# sensor_design.net
KiCad netlist of a schematic drawn in EasyEDA Pro
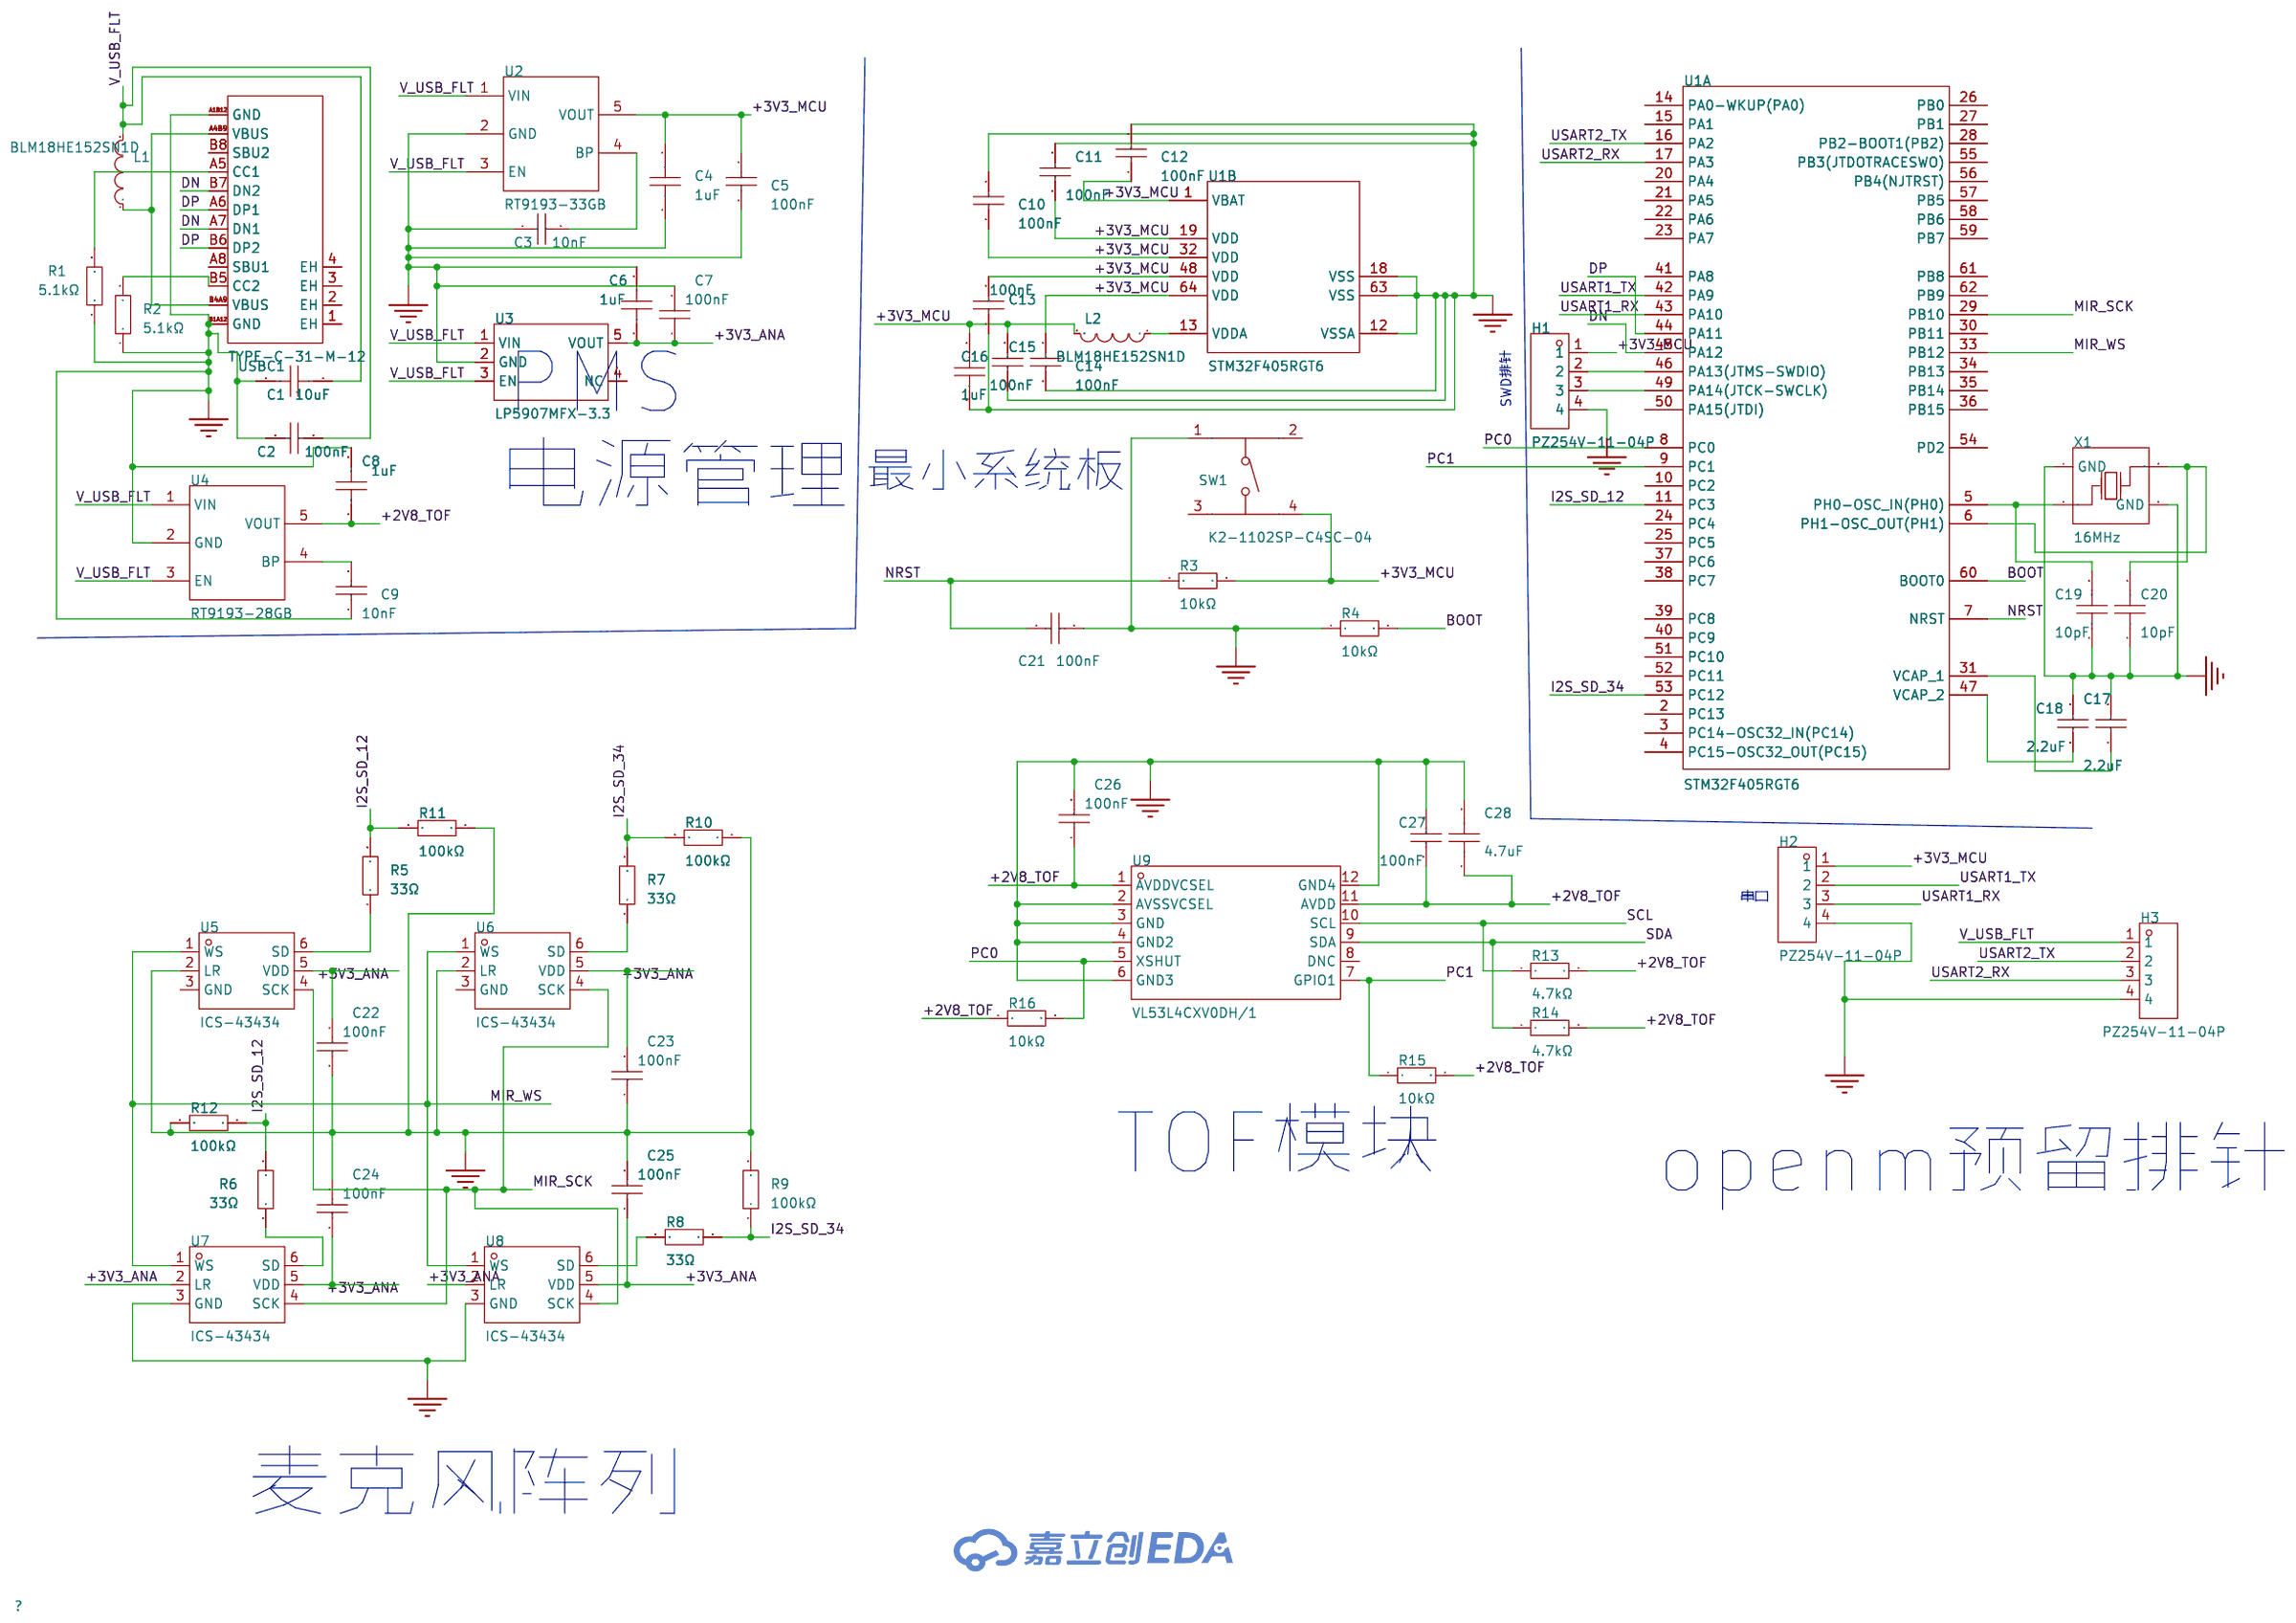
[diagram p0: schematic sheet]

(export (version "E")
  (design (tool "Eeschema 10.0.6"))
  (components
    (comp (ref "C1")
      (value "10uF")
      (footprint "easyedapro:C0805")
      (description "容值:10uF;精度:±10%;额定电压:16V;材质(温度系数):X5R;")
      (fields
        (field (name "Manufacturer Part") "GRM21BR61C106KE15L")
        (field (name "Manufacturer") "muRata(村田)")
      )
      (libsource (lib "easyedapro") (part "GRM21BR61C106KE15L"))
    )
    (comp (ref "C2")
      (value "100nF")
      (footprint "easyedapro:C0603")
      (description "容值:100nF;精度:±10%;额定电压:25V;温度系数:X7R;")
      (fields
        (field (name "Manufacturer Part") "CL10B104KA8NNNC")
        (field (name "Manufacturer") "SAMSUNG(三星)")
      )
      (libsource (lib "easyedapro") (part "CL10B104KA8NNNC"))
    )
    (comp (ref "C3")
      (value "10nF")
      (footprint "easyedapro:C0603")
      (description "容值:100nF;精度:±10%;额定电压:25V;温度系数:X7R;")
      (fields
        (field (name "Manufacturer Part") "CL10B104KA8NNNC")
        (field (name "Manufacturer") "SAMSUNG(三星)")
      )
      (libsource (lib "easyedapro") (part "CL10B104KA8NNNC"))
    )
    (comp (ref "C4")
      (value "1uF")
      (footprint "easyedapro:C0603")
      (description "容值:1uF;精度:±10%;额定电压:16V;温度系数:X7R;")
      (fields
        (field (name "Manufacturer Part") "GRM188R71C105KE15D")
        (field (name "Manufacturer") "muRata(村田)")
      )
      (libsource (lib "easyedapro") (part "GRM188R71C105KE15D"))
    )
    (comp (ref "C5")
      (value "100nF")
      (footprint "easyedapro:C0603")
      (description "容值:100nF;精度:±10%;额定电压:25V;温度系数:X7R;")
      (fields
        (field (name "Manufacturer Part") "CL10B104KA8NNNC")
        (field (name "Manufacturer") "SAMSUNG(三星)")
      )
      (libsource (lib "easyedapro") (part "CL10B104KA8NNNC"))
    )
    (comp (ref "C6")
      (value "1uF")
      (footprint "easyedapro:C0603")
      (description "容值:1uF;精度:±10%;额定电压:16V;温度系数:X7R;")
      (fields
        (field (name "Manufacturer Part") "GRM188R71C105KE15D")
        (field (name "Manufacturer") "muRata(村田)")
      )
      (libsource (lib "easyedapro") (part "GRM188R71C105KE15D"))
    )
    (comp (ref "C7")
      (value "100nF")
      (footprint "easyedapro:C0603")
      (description "容值:100nF;精度:±10%;额定电压:25V;温度系数:X7R;")
      (fields
        (field (name "Manufacturer Part") "CL10B104KA8NNNC")
        (field (name "Manufacturer") "SAMSUNG(三星)")
      )
      (libsource (lib "easyedapro") (part "CL10B104KA8NNNC"))
    )
    (comp (ref "C8")
      (value "1uF")
      (footprint "easyedapro:C0603")
      (description "容值:1uF;精度:±10%;额定电压:16V;温度系数:X7R;")
      (fields
        (field (name "Manufacturer Part") "GRM188R71C105KE15D")
        (field (name "Manufacturer") "muRata(村田)")
      )
      (libsource (lib "easyedapro") (part "GRM188R71C105KE15D"))
    )
    (comp (ref "C9")
      (value "10nF")
      (footprint "easyedapro:C0603")
      (description "容值:100nF;精度:±10%;额定电压:25V;温度系数:X7R;")
      (fields
        (field (name "Manufacturer Part") "CL10B104KA8NNNC")
        (field (name "Manufacturer") "SAMSUNG(三星)")
      )
      (libsource (lib "easyedapro") (part "CL10B104KA8NNNC"))
    )
    (comp (ref "C10")
      (value "100nF")
      (footprint "easyedapro:C0603")
      (description "容值:100nF;精度:±10%;额定电压:25V;温度系数:X7R;")
      (fields
        (field (name "Manufacturer Part") "CL10B104KA8NNNC")
        (field (name "Manufacturer") "SAMSUNG(三星)")
      )
      (libsource (lib "easyedapro") (part "CL10B104KA8NNNC"))
    )
    (comp (ref "C11")
      (value "100nF")
      (footprint "easyedapro:C0603")
      (description "容值:100nF;精度:±10%;额定电压:25V;温度系数:X7R;")
      (fields
        (field (name "Manufacturer Part") "CL10B104KA8NNNC")
        (field (name "Manufacturer") "SAMSUNG(三星)")
      )
      (libsource (lib "easyedapro") (part "CL10B104KA8NNNC"))
    )
    (comp (ref "C12")
      (value "100nF")
      (footprint "easyedapro:C0603")
      (description "容值:100nF;精度:±10%;额定电压:25V;温度系数:X7R;")
      (fields
        (field (name "Manufacturer Part") "CL10B104KA8NNNC")
        (field (name "Manufacturer") "SAMSUNG(三星)")
      )
      (libsource (lib "easyedapro") (part "CL10B104KA8NNNC"))
    )
    (comp (ref "C13")
      (value "100nF")
      (footprint "easyedapro:C0603")
      (description "容值:100nF;精度:±10%;额定电压:25V;温度系数:X7R;")
      (fields
        (field (name "Manufacturer Part") "CL10B104KA8NNNC")
        (field (name "Manufacturer") "SAMSUNG(三星)")
      )
      (libsource (lib "easyedapro") (part "CL10B104KA8NNNC"))
    )
    (comp (ref "C14")
      (value "100nF")
      (footprint "easyedapro:C0603")
      (description "容值:100nF;精度:±10%;额定电压:25V;温度系数:X7R;")
      (fields
        (field (name "Manufacturer Part") "CL10B104KA8NNNC")
        (field (name "Manufacturer") "SAMSUNG(三星)")
      )
      (libsource (lib "easyedapro") (part "CL10B104KA8NNNC"))
    )
    (comp (ref "C15")
      (value "100nF")
      (footprint "easyedapro:C0603")
      (description "容值:100nF;精度:±10%;额定电压:25V;温度系数:X7R;")
      (fields
        (field (name "Manufacturer Part") "CL10B104KA8NNNC")
        (field (name "Manufacturer") "SAMSUNG(三星)")
      )
      (libsource (lib "easyedapro") (part "CL10B104KA8NNNC"))
    )
    (comp (ref "C16")
      (value "1uF")
      (footprint "easyedapro:C0603")
      (description "容值:1uF;精度:±10%;额定电压:16V;温度系数:X7R;")
      (fields
        (field (name "Manufacturer Part") "GRM188R71C105KE15D")
        (field (name "Manufacturer") "muRata(村田)")
      )
      (libsource (lib "easyedapro") (part "GRM188R71C105KE15D"))
    )
    (comp (ref "C17")
      (value "2.2uF")
      (footprint "easyedapro:C0603")
      (description "容值:2.2uF;精度:±10%;额定电压:10V;温度系数:X5R;")
      (fields
        (field (name "Manufacturer Part") "CL10A225KP8NNNC")
        (field (name "Manufacturer") "SAMSUNG(三星)")
      )
      (libsource (lib "easyedapro") (part "CL10A225KP8NNNC"))
    )
    (comp (ref "C18")
      (value "2.2uF")
      (footprint "easyedapro:C0603")
      (description "容值:2.2uF;精度:±10%;额定电压:10V;温度系数:X5R;")
      (fields
        (field (name "Manufacturer Part") "CL10A225KP8NNNC")
        (field (name "Manufacturer") "SAMSUNG(三星)")
      )
      (libsource (lib "easyedapro") (part "CL10A225KP8NNNC"))
    )
    (comp (ref "C19")
      (value "10pF")
      (footprint "easyedapro:C0402")
      (description "容值:10pF;精度:±1%;额定电压:50V;温度系数:C0G;")
      (fields
        (field (name "Manufacturer Part") "GJM1555C1H100FB01D")
        (field (name "Manufacturer") "muRata(村田)")
      )
      (libsource (lib "easyedapro") (part "GJM1555C1H100FB01D"))
    )
    (comp (ref "C20")
      (value "10pF")
      (footprint "easyedapro:C0402")
      (description "容值:10pF;精度:±1%;额定电压:50V;温度系数:C0G;")
      (fields
        (field (name "Manufacturer Part") "GJM1555C1H100FB01D")
        (field (name "Manufacturer") "muRata(村田)")
      )
      (libsource (lib "easyedapro") (part "GJM1555C1H100FB01D"))
    )
    (comp (ref "C21")
      (value "100nF")
      (footprint "easyedapro:C0603")
      (description "容值:100nF;精度:±10%;额定电压:25V;温度系数:X7R;")
      (fields
        (field (name "Manufacturer Part") "CL10B104KA8NNNC")
        (field (name "Manufacturer") "SAMSUNG(三星)")
      )
      (libsource (lib "easyedapro") (part "CL10B104KA8NNNC"))
    )
    (comp (ref "C22")
      (value "100nF")
      (footprint "easyedapro:C0603")
      (description "容值:100nF;精度:±10%;额定电压:25V;温度系数:X7R;")
      (fields
        (field (name "Manufacturer Part") "CL10B104KA8NNNC")
        (field (name "Manufacturer") "SAMSUNG(三星)")
      )
      (libsource (lib "easyedapro") (part "CL10B104KA8NNNC"))
    )
    (comp (ref "C23")
      (value "100nF")
      (footprint "easyedapro:C0603")
      (description "容值:100nF;精度:±10%;额定电压:25V;温度系数:X7R;")
      (fields
        (field (name "Manufacturer Part") "CL10B104KA8NNNC")
        (field (name "Manufacturer") "SAMSUNG(三星)")
      )
      (libsource (lib "easyedapro") (part "CL10B104KA8NNNC"))
    )
    (comp (ref "C24")
      (value "100nF")
      (footprint "easyedapro:C0603")
      (description "容值:100nF;精度:±10%;额定电压:25V;温度系数:X7R;")
      (fields
        (field (name "Manufacturer Part") "CL10B104KA8NNNC")
        (field (name "Manufacturer") "SAMSUNG(三星)")
      )
      (libsource (lib "easyedapro") (part "CL10B104KA8NNNC"))
    )
    (comp (ref "C25")
      (value "100nF")
      (footprint "easyedapro:C0603")
      (description "容值:100nF;精度:±10%;额定电压:25V;温度系数:X7R;")
      (fields
        (field (name "Manufacturer Part") "CL10B104KA8NNNC")
        (field (name "Manufacturer") "SAMSUNG(三星)")
      )
      (libsource (lib "easyedapro") (part "CL10B104KA8NNNC"))
    )
    (comp (ref "C26")
      (value "100nF")
      (footprint "easyedapro:C0603")
      (description "容值:100nF;精度:±10%;额定电压:25V;温度系数:X7R;")
      (fields
        (field (name "Manufacturer Part") "CGA0402X7R104K250GT")
        (field (name "Manufacturer") "HRE(芯声)")
      )
      (libsource (lib "easyedapro") (part "CL10B104KA8NNNC"))
    )
    (comp (ref "C27")
      (value "100nF")
      (footprint "easyedapro:C0603")
      (description "容值:100nF;精度:±10%;额定电压:25V;温度系数:X7R;")
      (fields
        (field (name "Manufacturer Part") "CGA0402X7R104K250GT")
        (field (name "Manufacturer") "HRE(芯声)")
      )
      (libsource (lib "easyedapro") (part "CL10B104KA8NNNC"))
    )
    (comp (ref "C28")
      (value "4.7uF")
      (footprint "easyedapro:C0603")
      (description "容值:4.7uF;精度:±10%;额定电压:16V;温度系数:X7R;")
      (fields
        (field (name "Manufacturer Part") "GRM188Z71C475KE21D")
        (field (name "Manufacturer") "muRata(村田)")
      )
      (libsource (lib "easyedapro") (part "GRM188Z71C475KE21D"))
    )
    (comp (ref "H1")
      (value "PZ254V-11-04P")
      (footprint "easyedapro:HDR-TH_4P-P2.54-V-M")
      (fields (field (name "Manufacturer") "XFCN(兴飞)"))
      (libsource (lib "easyedapro") (part "PZ254V-11-04P_C2691448"))
    )
    (comp (ref "H2")
      (value "PZ254V-11-04P")
      (footprint "easyedapro:HDR-TH_4P-P2.54-V-M")
      (fields (field (name "Manufacturer") "XFCN(兴飞)"))
      (libsource (lib "easyedapro") (part "PZ254V-11-04P_C2691448"))
    )
    (comp (ref "H3")
      (value "PZ254V-11-04P")
      (footprint "easyedapro:HDR-TH_4P-P2.54-V-M")
      (fields (field (name "Manufacturer") "XFCN(兴飞)"))
      (libsource (lib "easyedapro") (part "PZ254V-11-04P_C2691448"))
    )
    (comp (ref "L1")
      (value "BLM18HE152SN1D")
      (footprint "easyedapro:L0603")
      (description "标称阻抗@测试频率:1.5kΩ@100MHz;误差:±25%;直流电阻(RDC):500mΩ;")
      (fields (field (name "Manufacturer") "muRata(村田)"))
      (libsource (lib "easyedapro") (part "BLM18HE152SN1D"))
    )
    (comp (ref "L2")
      (value "BLM18HE152SN1D")
      (footprint "easyedapro:L0603")
      (description "标称阻抗@测试频率:1.5kΩ@100MHz;误差:±25%;直流电阻(RDC):500mΩ;")
      (fields (field (name "Manufacturer") "muRata(村田)"))
      (libsource (lib "easyedapro") (part "BLM18HE152SN1D"))
    )
    (comp (ref "R1")
      (value "5.1kΩ")
      (footprint "easyedapro:R0603")
      (description "电阻类型:厚膜电阻;阻值:5.1kΩ;精度:±1%;功率:100mW;工作电压:75V;温度系数:±100ppm/°C;")
      (fields (field (name "Manufacturer Part") "RC0603FR-075K1L") (field (name "Manufacturer") "YAGEO(国巨)"))
      (libsource (lib "easyedapro") (part "RC0603FR-075K1L"))
    )
    (comp (ref "R2")
      (value "5.1kΩ")
      (footprint "easyedapro:R0603")
      (description "电阻类型:厚膜电阻;阻值:5.1kΩ;精度:±1%;功率:100mW;工作电压:75V;温度系数:±100ppm/°C;")
      (fields (field (name "Manufacturer Part") "RC0603FR-075K1L") (field (name "Manufacturer") "YAGEO(国巨)"))
      (libsource (lib "easyedapro") (part "RC0603FR-075K1L"))
    )
    (comp (ref "R3")
      (value "10kΩ")
      (footprint "easyedapro:R0603")
      (description "电阻类型:厚膜电阻;阻值:10kΩ;精度:±1%;功率:100mW;工作电压:75V;温度系数:±100ppm/°C;")
      (fields
        (field (name "Manufacturer Part") "0603WAF1002T5E")
        (field (name "Manufacturer") "UNI-ROYAL(厚声)")
      )
      (libsource (lib "easyedapro") (part "0603WAF1002T5E"))
    )
    (comp (ref "R4")
      (value "10kΩ")
      (footprint "easyedapro:R0603")
      (description "电阻类型:厚膜电阻;阻值:10kΩ;精度:±1%;功率:100mW;工作电压:75V;温度系数:±100ppm/°C;")
      (fields
        (field (name "Manufacturer Part") "0603WAF1002T5E")
        (field (name "Manufacturer") "UNI-ROYAL(厚声)")
      )
      (libsource (lib "easyedapro") (part "0603WAF1002T5E"))
    )
    (comp (ref "R5")
      (value "33Ω")
      (footprint "easyedapro:R0603")
      (description "电阻类型:厚膜电阻;阻值:3.3kΩ;精度:±1%;功率:100mW;工作电压:75V;温度系数:±100ppm/°C;")
      (fields
        (field (name "Manufacturer Part") "0603WAF330JT5E")
        (field (name "Manufacturer") "UNI-ROYAL(厚声)")
      )
      (libsource (lib "easyedapro") (part "0603WAF3301T5E"))
    )
    (comp (ref "R6")
      (value "33Ω")
      (footprint "easyedapro:R0603")
      (description "电阻类型:厚膜电阻;阻值:3.3kΩ;精度:±1%;功率:100mW;工作电压:75V;温度系数:±100ppm/°C;")
      (fields
        (field (name "Manufacturer Part") "0603WAF330JT5E")
        (field (name "Manufacturer") "UNI-ROYAL(厚声)")
      )
      (libsource (lib "easyedapro") (part "0603WAF3301T5E"))
    )
    (comp (ref "R7")
      (value "33Ω")
      (footprint "easyedapro:R0603")
      (description "电阻类型:厚膜电阻;阻值:3.3kΩ;精度:±1%;功率:100mW;工作电压:75V;温度系数:±100ppm/°C;")
      (fields
        (field (name "Manufacturer Part") "0603WAF330JT5E")
        (field (name "Manufacturer") "UNI-ROYAL(厚声)")
      )
      (libsource (lib "easyedapro") (part "0603WAF3301T5E"))
    )
    (comp (ref "R8")
      (value "33Ω")
      (footprint "easyedapro:R0603")
      (description "电阻类型:厚膜电阻;阻值:3.3kΩ;精度:±1%;功率:100mW;工作电压:75V;温度系数:±100ppm/°C;")
      (fields
        (field (name "Manufacturer Part") "0603WAF330JT5E")
        (field (name "Manufacturer") "UNI-ROYAL(厚声)")
      )
      (libsource (lib "easyedapro") (part "0603WAF3301T5E"))
    )
    (comp (ref "R9")
      (value "100kΩ")
      (footprint "easyedapro:R0603")
      (description "电阻类型:厚膜电阻;阻值:100kΩ;精度:±1%;功率:100mW;工作电压:75V;温度系数:±100ppm/°C;")
      (fields
        (field (name "Manufacturer Part") "0603WAF1003T5E")
        (field (name "Manufacturer") "UNI-ROYAL(厚声)")
      )
      (libsource (lib "easyedapro") (part "0603WAF1003T5E"))
    )
    (comp (ref "R10")
      (value "100kΩ")
      (footprint "easyedapro:R0603")
      (description "电阻类型:厚膜电阻;阻值:100kΩ;精度:±1%;功率:100mW;工作电压:75V;温度系数:±100ppm/°C;")
      (fields
        (field (name "Manufacturer Part") "0603WAF1003T5E")
        (field (name "Manufacturer") "UNI-ROYAL(厚声)")
      )
      (libsource (lib "easyedapro") (part "0603WAF1003T5E"))
    )
    (comp (ref "R11")
      (value "100kΩ")
      (footprint "easyedapro:R0603")
      (description "电阻类型:厚膜电阻;阻值:100kΩ;精度:±1%;功率:100mW;工作电压:75V;温度系数:±100ppm/°C;")
      (fields
        (field (name "Manufacturer Part") "0603WAF1003T5E")
        (field (name "Manufacturer") "UNI-ROYAL(厚声)")
      )
      (libsource (lib "easyedapro") (part "0603WAF1003T5E"))
    )
    (comp (ref "R12")
      (value "100kΩ")
      (footprint "easyedapro:R0603")
      (description "电阻类型:厚膜电阻;阻值:100kΩ;精度:±1%;功率:100mW;工作电压:75V;温度系数:±100ppm/°C;")
      (fields
        (field (name "Manufacturer Part") "0603WAF1003T5E")
        (field (name "Manufacturer") "UNI-ROYAL(厚声)")
      )
      (libsource (lib "easyedapro") (part "0603WAF1003T5E"))
    )
    (comp (ref "R13")
      (value "4.7kΩ")
      (footprint "easyedapro:R0603")
      (description "电阻类型:厚膜电阻;阻值:4.7kΩ;精度:±1%;功率:100mW;工作电压:75V;温度系数:±100ppm/°C;")
      (fields
        (field (name "Manufacturer Part") "0603WAF4701T5E")
        (field (name "Manufacturer") "UNI-ROYAL(厚声)")
      )
      (libsource (lib "easyedapro") (part "0603WAF4701T5E"))
    )
    (comp (ref "R14")
      (value "4.7kΩ")
      (footprint "easyedapro:R0603")
      (description "电阻类型:厚膜电阻;阻值:4.7kΩ;精度:±1%;功率:100mW;工作电压:75V;温度系数:±100ppm/°C;")
      (fields
        (field (name "Manufacturer Part") "0603WAF4701T5E")
        (field (name "Manufacturer") "UNI-ROYAL(厚声)")
      )
      (libsource (lib "easyedapro") (part "0603WAF4701T5E"))
    )
    (comp (ref "R15")
      (value "10kΩ")
      (footprint "easyedapro:R0603")
      (description "电阻类型:厚膜电阻;阻值:10kΩ;精度:±1%;功率:100mW;工作电压:75V;温度系数:±100ppm/°C;")
      (fields
        (field (name "Manufacturer Part") "0603WAF1002T5E")
        (field (name "Manufacturer") "UNI-ROYAL(厚声)")
      )
      (libsource (lib "easyedapro") (part "0603WAF1002T5E"))
    )
    (comp (ref "R16")
      (value "10kΩ")
      (footprint "easyedapro:R0603")
      (description "电阻类型:厚膜电阻;阻值:10kΩ;精度:±1%;功率:100mW;工作电压:75V;温度系数:±100ppm/°C;")
      (fields
        (field (name "Manufacturer Part") "0603WAF1002T5E")
        (field (name "Manufacturer") "UNI-ROYAL(厚声)")
      )
      (libsource (lib "easyedapro") (part "0603WAF1002T5E"))
    )
    (comp (ref "SW1")
      (value "K2-1102SP-C4SC-04")
      (footprint "easyedapro:KEY-SMD_4P-L6.0-W6.0-P4.50-LS9.5-BL")
      (description "电路结构:单刀单掷;按钮形状:圆形按钮;作用力:2.5N;安装方式:立贴;开关长度:6mm;开关宽度:6mm;开关高度:5mm;触点电流:50mA;额定电压:12V;带灯:-;工作寿命:10万次;")
      (fields (field (name "Manufacturer") "韩国韩荣"))
      (libsource (lib "easyedapro") (part "K2-1102SP-C4SC-04"))
    )
    (comp (ref "U1")
      (value "STM32F405RGT6")
      (footprint "easyedapro:LQFP-64_L10.0-W10.0-P0.50-LS12.0-BL")
      (description "CPU内核:ARM-M4;CPU最大主频:168MHz;应用领域:-;")
      (fields (field (name "Manufacturer") "ST(意法半导体)"))
      (libsource (lib "easyedapro") (part "STM32F405RGT6"))
    )
    (comp (ref "U2")
      (value "RT9193-33GB")
      (footprint "easyedapro:SOT-23-5_L3.0-W1.7-P0.95-LS2.8-BL")
      (description "输出类型:固定;工作电压:5.5V;输出电压:3.3V;输出电流:300mA;电源纹波抑制比(PSRR):-50dB@(10kHz);输出极性:正极;")
      (fields (field (name "Manufacturer") "RICHTEK(立锜)"))
      (libsource (lib "easyedapro") (part "RT9193-33GB"))
    )
    (comp (ref "U3")
      (value "LP5907MFX-3.3")
      (footprint "easyedapro:SOT-23-5_L3.0-W1.7-P0.95-LS2.8-BR")
      (description "输出类型:固定;工作电压:5.5V;输出电压:3.3V;输出电流:300mA;电源纹波抑制比(PSRR):75dB@(1kHz);输出极性:正极;")
      (fields (field (name "Manufacturer") "TECH PUBLIC(台舟)"))
      (libsource (lib "easyedapro") (part "LP5907MFX-3.3"))
    )
    (comp (ref "U4")
      (value "RT9193-28GB")
      (footprint "easyedapro:SOT-23-5_L3.0-W1.7-P0.95-LS2.8-BR")
      (description "输出类型:固定;工作电压:5.5V;输出电压:2.8V;输出电流:300mA;电源纹波抑制比(PSRR):50dB@(10kHz);输出极性:正极;")
      (fields (field (name "Manufacturer") "RICHTEK(立锜)"))
      (libsource (lib "easyedapro") (part "RT9193-28GB"))
    )
    (comp (ref "U5")
      (value "ICS-43434")
      (footprint "easyedapro:MIC-SMD_6P-L3.5-W2.7-P0.90-BL")
      (description "指向性:全指向;信噪比:64dB;灵敏度:-;")
      (fields (field (name "Manufacturer") "TDK InvenSense(应美盛)"))
      (libsource (lib "easyedapro") (part "ICS-43434_C5656610"))
    )
    (comp (ref "U6")
      (value "ICS-43434")
      (footprint "easyedapro:MIC-SMD_6P-L3.5-W2.7-P0.90-BL")
      (description "指向性:全指向;信噪比:64dB;灵敏度:-;")
      (fields (field (name "Manufacturer") "TDK InvenSense(应美盛)"))
      (libsource (lib "easyedapro") (part "ICS-43434_C5656610"))
    )
    (comp (ref "U7")
      (value "ICS-43434")
      (footprint "easyedapro:MIC-SMD_6P-L3.5-W2.7-P0.90-BL")
      (description "指向性:全指向;信噪比:64dB;灵敏度:-;")
      (fields (field (name "Manufacturer") "TDK InvenSense(应美盛)"))
      (libsource (lib "easyedapro") (part "ICS-43434_C5656610"))
    )
    (comp (ref "U8")
      (value "ICS-43434")
      (footprint "easyedapro:MIC-SMD_6P-L3.5-W2.7-P0.90-BL")
      (description "指向性:全指向;信噪比:64dB;灵敏度:-;")
      (fields (field (name "Manufacturer") "TDK InvenSense(应美盛)"))
      (libsource (lib "easyedapro") (part "ICS-43434_C5656610"))
    )
    (comp (ref "U9")
      (value "VL53L4CXV0DH/1")
      (footprint "easyedapro:OPTO-SMD_VL53L1CXV0FY-1")
      (description "线性范围:0m~6m;")
      (fields (field (name "Manufacturer") "ST(意法半导体)"))
      (libsource (lib "easyedapro") (part "VL53L4CXV0DH/1"))
    )
    (comp (ref "USBC1")
      (value "TYPE-C-31-M-12")
      (footprint "easyedapro:USB-C_SMD-TYPE-C-31-M-12_1")
      (description "连接器类型:Type-C;协议标准:-;公母:母;安装方式:-;触点数量:16P;端口数量:1;额定电流 - 电源:5A;工作温度:-;")
      (fields (field (name "Manufacturer") "韩国韩荣"))
      (libsource (lib "easyedapro") (part "TYPE-C-31-M-12"))
    )
    (comp (ref "X1")
      (value "16MHz")
      (footprint "easyedapro:CRYSTAL-SMD_4P-L3.2-W2.5-BL")
      (description "频率:16MHz;常温频差:±10ppm;负载电容:9pF;频率稳定度:±18ppm;")
      (fields
        (field (name "Manufacturer Part") "TSX-3225 16.0000MF18X-AC3")
        (field (name "Manufacturer") "EPSON(爱普生)")
      )
      (libsource (lib "easyedapro") (part "TSX-3225 16.0000MF18X-AC3"))
    )
  )
  (nets
    (net (code "1") (name "/+2V8_TOF") (class "Default")
      (node (ref "C26") (pin "1") (pinfunction "1_1") (pintype "input"))
      (node (ref "C27") (pin "1") (pinfunction "1_1") (pintype "input"))
      (node (ref "C28") (pin "1") (pinfunction "1_1") (pintype "unspecified"))
      (node (ref "C8") (pin "1") (pinfunction "1_1") (pintype "unspecified"))
      (node (ref "R13") (pin "2") (pinfunction "2_2") (pintype "input"))
      (node (ref "R14") (pin "2") (pinfunction "2_2") (pintype "input"))
      (node (ref "R15") (pin "2") (pinfunction "2_2") (pintype "input"))
      (node (ref "R16") (pin "1") (pinfunction "1_1") (pintype "input"))
      (node (ref "U4") (pin "5") (pinfunction "VOUT_5") (pintype "unspecified"))
      (node (ref "U9") (pin "1") (pinfunction "AVDDVCSEL_1") (pintype "unspecified"))
      (node (ref "U9") (pin "11") (pinfunction "AVDD_11") (pintype "unspecified"))
    )
    (net (code "2") (name "/+3V3_ANA") (class "Default")
      (node (ref "C22") (pin "2") (pinfunction "2_2") (pintype "input"))
      (node (ref "C23") (pin "2") (pinfunction "2_2") (pintype "input"))
      (node (ref "C24") (pin "1") (pinfunction "1_1") (pintype "input"))
      (node (ref "C25") (pin "1") (pinfunction "1_1") (pintype "input"))
      (node (ref "C6") (pin "1") (pinfunction "1_1") (pintype "unspecified"))
      (node (ref "C7") (pin "1") (pinfunction "1_1") (pintype "input"))
      (node (ref "U3") (pin "5") (pinfunction "VOUT_5") (pintype "unspecified"))
      (node (ref "U5") (pin "5") (pinfunction "VDD_5") (pintype "unspecified"))
      (node (ref "U6") (pin "5") (pinfunction "VDD_5") (pintype "unspecified"))
      (node (ref "U7") (pin "2") (pinfunction "LR_2") (pintype "unspecified"))
      (node (ref "U7") (pin "5") (pinfunction "VDD_5") (pintype "unspecified"))
      (node (ref "U8") (pin "2") (pinfunction "LR_2") (pintype "unspecified"))
      (node (ref "U8") (pin "5") (pinfunction "VDD_5") (pintype "unspecified"))
    )
    (net (code "3") (name "/+3V3_MCU") (class "Default")
      (node (ref "C10") (pin "1") (pinfunction "1_1") (pintype "input"))
      (node (ref "C11") (pin "1") (pinfunction "1_1") (pintype "input"))
      (node (ref "C12") (pin "1") (pinfunction "1_1") (pintype "input"))
      (node (ref "C13") (pin "2") (pinfunction "2_2") (pintype "input"))
      (node (ref "C14") (pin "2") (pinfunction "2_2") (pintype "input"))
      (node (ref "C15") (pin "2") (pinfunction "2_2") (pintype "input"))
      (node (ref "C16") (pin "2") (pinfunction "2_2") (pintype "unspecified"))
      (node (ref "C4") (pin "2") (pinfunction "2_2") (pintype "unspecified"))
      (node (ref "C5") (pin "2") (pinfunction "2_2") (pintype "input"))
      (node (ref "H1") (pin "1") (pinfunction "1_1") (pintype "unspecified"))
      (node (ref "H2") (pin "1") (pinfunction "1_1") (pintype "unspecified"))
      (node (ref "L2") (pin "2") (pinfunction "2_2") (pintype "unspecified"))
      (node (ref "R3") (pin "2") (pinfunction "2_2") (pintype "input"))
      (node (ref "SW1") (pin "4") (pinfunction "4_4") (pintype "unspecified"))
      (node (ref "U1") (pin "1") (pinfunction "VBAT_1") (pintype "unspecified"))
      (node (ref "U1") (pin "19") (pinfunction "VDD_19") (pintype "unspecified"))
      (node (ref "U1") (pin "32") (pinfunction "VDD_32") (pintype "unspecified"))
      (node (ref "U1") (pin "48") (pinfunction "VDD_48") (pintype "unspecified"))
      (node (ref "U1") (pin "64") (pinfunction "VDD_64") (pintype "unspecified"))
      (node (ref "U2") (pin "5") (pinfunction "VOUT_5") (pintype "unspecified"))
    )
    (net (code "4") (name "/BOOT") (class "Default")
      (node (ref "R4") (pin "2") (pinfunction "2_2") (pintype "input"))
      (node (ref "U1") (pin "60") (pinfunction "BOOT0_60") (pintype "unspecified"))
    )
    (net (code "5") (name "/DN") (class "Default")
      (node (ref "U1") (pin "45") (pinfunction "PA12_45") (pintype "bidirectional"))
      (node (ref "USBC1") (pin "A7") (pinfunction "DN1_A7") (pintype "unspecified"))
      (node (ref "USBC1") (pin "B7") (pinfunction "DN2_B7") (pintype "unspecified"))
    )
    (net (code "6") (name "/DP") (class "Default")
      (node (ref "U1") (pin "44") (pinfunction "PA11_44") (pintype "bidirectional"))
      (node (ref "USBC1") (pin "A6") (pinfunction "DP1_A6") (pintype "unspecified"))
      (node (ref "USBC1") (pin "B6") (pinfunction "DP2_B6") (pintype "unspecified"))
    )
    (net (code "7") (name "/I2S_SD_12") (class "Default")
      (node (ref "R11") (pin "2") (pinfunction "2_2") (pintype "input"))
      (node (ref "R12") (pin "1") (pinfunction "1_1") (pintype "input"))
      (node (ref "R5") (pin "2") (pinfunction "2_2") (pintype "input"))
      (node (ref "R6") (pin "2") (pinfunction "2_2") (pintype "input"))
      (node (ref "U1") (pin "11") (pinfunction "PC3_11") (pintype "bidirectional"))
    )
    (net (code "8") (name "/I2S_SD_34") (class "Default")
      (node (ref "R10") (pin "2") (pinfunction "2_2") (pintype "input"))
      (node (ref "R7") (pin "2") (pinfunction "2_2") (pintype "input"))
      (node (ref "R8") (pin "1") (pinfunction "1_1") (pintype "input"))
      (node (ref "R9") (pin "1") (pinfunction "1_1") (pintype "input"))
      (node (ref "U1") (pin "53") (pinfunction "PC12_53") (pintype "bidirectional"))
    )
    (net (code "9") (name "/MIR_SCK") (class "Default")
      (node (ref "U1") (pin "29") (pinfunction "PB10_29") (pintype "bidirectional"))
      (node (ref "U5") (pin "4") (pinfunction "SCK_4") (pintype "unspecified"))
      (node (ref "U6") (pin "4") (pinfunction "SCK_4") (pintype "unspecified"))
      (node (ref "U7") (pin "4") (pinfunction "SCK_4") (pintype "unspecified"))
      (node (ref "U8") (pin "4") (pinfunction "SCK_4") (pintype "unspecified"))
    )
    (net (code "10") (name "/MIR_WS") (class "Default")
      (node (ref "U1") (pin "33") (pinfunction "PB12_33") (pintype "bidirectional"))
      (node (ref "U5") (pin "1") (pinfunction "WS_1") (pintype "unspecified"))
      (node (ref "U6") (pin "1") (pinfunction "WS_1") (pintype "unspecified"))
      (node (ref "U7") (pin "1") (pinfunction "WS_1") (pintype "unspecified"))
      (node (ref "U8") (pin "1") (pinfunction "WS_1") (pintype "unspecified"))
    )
    (net (code "11") (name "/NRST") (class "Default")
      (node (ref "C21") (pin "2") (pinfunction "2_2") (pintype "input"))
      (node (ref "R3") (pin "1") (pinfunction "1_1") (pintype "input"))
      (node (ref "U1") (pin "7") (pinfunction "NRST_7") (pintype "bidirectional"))
    )
    (net (code "12") (name "/PC0") (class "Default")
      (node (ref "R16") (pin "2") (pinfunction "2_2") (pintype "input"))
      (node (ref "U1") (pin "8") (pinfunction "PC0_8") (pintype "bidirectional"))
      (node (ref "U9") (pin "5") (pinfunction "XSHUT_5") (pintype "unspecified"))
    )
    (net (code "13") (name "/PC1") (class "Default")
      (node (ref "R15") (pin "1") (pinfunction "1_1") (pintype "input"))
      (node (ref "U1") (pin "9") (pinfunction "PC1_9") (pintype "bidirectional"))
      (node (ref "U9") (pin "7") (pinfunction "GPIO1_7") (pintype "unspecified"))
    )
    (net (code "14") (name "/SCL") (class "Default")
      (node (ref "R13") (pin "1") (pinfunction "1_1") (pintype "input"))
      (node (ref "U9") (pin "10") (pinfunction "SCL_10") (pintype "unspecified"))
    )
    (net (code "15") (name "/SDA") (class "Default")
      (node (ref "R14") (pin "1") (pinfunction "1_1") (pintype "input"))
      (node (ref "U9") (pin "9") (pinfunction "SDA_9") (pintype "unspecified"))
    )
    (net (code "16") (name "/USART1_RX") (class "Default")
      (node (ref "H2") (pin "3") (pinfunction "3_3") (pintype "unspecified"))
      (node (ref "U1") (pin "43") (pinfunction "PA10_43") (pintype "bidirectional"))
    )
    (net (code "17") (name "/USART1_TX") (class "Default")
      (node (ref "H2") (pin "2") (pinfunction "2_2") (pintype "unspecified"))
      (node (ref "U1") (pin "42") (pinfunction "PA9_42") (pintype "bidirectional"))
    )
    (net (code "18") (name "/USART2_RX") (class "Default")
      (node (ref "H3") (pin "3") (pinfunction "3_3") (pintype "unspecified"))
      (node (ref "U1") (pin "17") (pinfunction "PA3_17") (pintype "bidirectional"))
    )
    (net (code "19") (name "/USART2_TX") (class "Default")
      (node (ref "H3") (pin "2") (pinfunction "2_2") (pintype "unspecified"))
      (node (ref "U1") (pin "16") (pinfunction "PA2_16") (pintype "bidirectional"))
    )
    (net (code "20") (name "/V_USB_FLT") (class "Default")
      (node (ref "C1") (pin "2") (pinfunction "2_2") (pintype "unspecified"))
      (node (ref "C2") (pin "2") (pinfunction "2_2") (pintype "input"))
      (node (ref "H3") (pin "1") (pinfunction "1_1") (pintype "unspecified"))
      (node (ref "L1") (pin "2") (pinfunction "2_2") (pintype "unspecified"))
      (node (ref "U2") (pin "1") (pinfunction "VIN_1") (pintype "unspecified"))
      (node (ref "U2") (pin "3") (pinfunction "EN_3") (pintype "unspecified"))
      (node (ref "U3") (pin "1") (pinfunction "VIN_1") (pintype "unspecified"))
      (node (ref "U3") (pin "3") (pinfunction "EN_3") (pintype "unspecified"))
      (node (ref "U4") (pin "1") (pinfunction "VIN_1") (pintype "unspecified"))
      (node (ref "U4") (pin "3") (pinfunction "EN_3") (pintype "unspecified"))
    )
    (net (code "21") (name "GND") (class "Default")
      (node (ref "C1") (pin "1") (pinfunction "1_1") (pintype "unspecified"))
      (node (ref "C10") (pin "2") (pinfunction "2_2") (pintype "input"))
      (node (ref "C11") (pin "2") (pinfunction "2_2") (pintype "input"))
      (node (ref "C12") (pin "2") (pinfunction "2_2") (pintype "input"))
      (node (ref "C13") (pin "1") (pinfunction "1_1") (pintype "input"))
      (node (ref "C14") (pin "1") (pinfunction "1_1") (pintype "input"))
      (node (ref "C15") (pin "1") (pinfunction "1_1") (pintype "input"))
      (node (ref "C16") (pin "1") (pinfunction "1_1") (pintype "unspecified"))
      (node (ref "C17") (pin "2") (pinfunction "2_2") (pintype "input"))
      (node (ref "C18") (pin "2") (pinfunction "2_2") (pintype "input"))
      (node (ref "C19") (pin "1") (pinfunction "1_1") (pintype "unspecified"))
      (node (ref "C2") (pin "1") (pinfunction "1_1") (pintype "input"))
      (node (ref "C20") (pin "1") (pinfunction "1_1") (pintype "unspecified"))
      (node (ref "C21") (pin "1") (pinfunction "1_1") (pintype "input"))
      (node (ref "C22") (pin "1") (pinfunction "1_1") (pintype "input"))
      (node (ref "C23") (pin "1") (pinfunction "1_1") (pintype "input"))
      (node (ref "C24") (pin "2") (pinfunction "2_2") (pintype "input"))
      (node (ref "C25") (pin "2") (pinfunction "2_2") (pintype "input"))
      (node (ref "C26") (pin "2") (pinfunction "2_2") (pintype "input"))
      (node (ref "C27") (pin "2") (pinfunction "2_2") (pintype "input"))
      (node (ref "C28") (pin "2") (pinfunction "2_2") (pintype "unspecified"))
      (node (ref "C3") (pin "1") (pinfunction "1_1") (pintype "input"))
      (node (ref "C4") (pin "1") (pinfunction "1_1") (pintype "unspecified"))
      (node (ref "C5") (pin "1") (pinfunction "1_1") (pintype "input"))
      (node (ref "C6") (pin "2") (pinfunction "2_2") (pintype "unspecified"))
      (node (ref "C7") (pin "2") (pinfunction "2_2") (pintype "input"))
      (node (ref "C8") (pin "2") (pinfunction "2_2") (pintype "unspecified"))
      (node (ref "C9") (pin "1") (pinfunction "1_1") (pintype "input"))
      (node (ref "H1") (pin "4") (pinfunction "4_4") (pintype "unspecified"))
      (node (ref "H2") (pin "4") (pinfunction "4_4") (pintype "unspecified"))
      (node (ref "H3") (pin "4") (pinfunction "4_4") (pintype "unspecified"))
      (node (ref "R1") (pin "1") (pinfunction "1_1") (pintype "input"))
      (node (ref "R10") (pin "1") (pinfunction "1_1") (pintype "input"))
      (node (ref "R11") (pin "1") (pinfunction "1_1") (pintype "input"))
      (node (ref "R12") (pin "2") (pinfunction "2_2") (pintype "input"))
      (node (ref "R2") (pin "1") (pinfunction "1_1") (pintype "input"))
      (node (ref "R4") (pin "1") (pinfunction "1_1") (pintype "input"))
      (node (ref "R9") (pin "2") (pinfunction "2_2") (pintype "input"))
      (node (ref "SW1") (pin "1") (pinfunction "1_1") (pintype "unspecified"))
      (node (ref "U1") (pin "12") (pinfunction "VSSA_12") (pintype "unspecified"))
      (node (ref "U1") (pin "18") (pinfunction "VSS_18") (pintype "unspecified"))
      (node (ref "U1") (pin "63") (pinfunction "VSS_63") (pintype "unspecified"))
      (node (ref "U2") (pin "2") (pinfunction "GND_2") (pintype "unspecified"))
      (node (ref "U3") (pin "2") (pinfunction "GND_2") (pintype "unspecified"))
      (node (ref "U4") (pin "2") (pinfunction "GND_2") (pintype "unspecified"))
      (node (ref "U5") (pin "2") (pinfunction "LR_2") (pintype "unspecified"))
      (node (ref "U6") (pin "2") (pinfunction "LR_2") (pintype "unspecified"))
      (node (ref "U7") (pin "3") (pinfunction "GND_3") (pintype "unspecified"))
      (node (ref "U8") (pin "3") (pinfunction "GND_3") (pintype "unspecified"))
      (node (ref "U9") (pin "12") (pinfunction "GND4_12") (pintype "unspecified"))
      (node (ref "U9") (pin "2") (pinfunction "AVSSVCSEL_2") (pintype "unspecified"))
      (node (ref "U9") (pin "3") (pinfunction "GND_3") (pintype "unspecified"))
      (node (ref "U9") (pin "4") (pinfunction "GND2_4") (pintype "unspecified"))
      (node (ref "U9") (pin "6") (pinfunction "GND3_6") (pintype "unspecified"))
      (node (ref "USBC1") (pin "A1B12") (pinfunction "GND_A1B12") (pintype "unspecified"))
      (node (ref "USBC1") (pin "B1A12") (pinfunction "GND_B1A12") (pintype "unspecified"))
      (node (ref "X1") (pin "2") (pinfunction "GND_2") (pintype "input"))
      (node (ref "X1") (pin "4") (pinfunction "GND_4") (pintype "input"))
    )
    (net (code "22") (name "Net-(L1-Pad1)") (class "Default")
      (node (ref "L1") (pin "1") (pinfunction "1_1") (pintype "unspecified"))
      (node (ref "USBC1") (pin "A4B9") (pinfunction "VBUS_A4B9") (pintype "unspecified"))
      (node (ref "USBC1") (pin "B4A9") (pinfunction "VBUS_B4A9") (pintype "unspecified"))
    )
    (net (code "23") (name "Net-(U1A-PA13(JTMS-SWDIO))") (class "Default")
      (node (ref "H1") (pin "2") (pinfunction "2_2") (pintype "unspecified"))
      (node (ref "U1") (pin "46") (pinfunction "PA13(JTMS-SWDIO)_46") (pintype "bidirectional"))
    )
    (net (code "24") (name "Net-(U1A-PA14(JTCK-SWCLK))") (class "Default")
      (node (ref "H1") (pin "3") (pinfunction "3_3") (pintype "unspecified"))
      (node (ref "U1") (pin "49") (pinfunction "PA14(JTCK-SWCLK)_49") (pintype "bidirectional"))
    )
    (net (code "25") (name "Net-(U1A-PH0-OSC_IN(PH0))") (class "Default")
      (node (ref "C19") (pin "2") (pinfunction "2_2") (pintype "unspecified"))
      (node (ref "U1") (pin "5") (pinfunction "PH0-OSC_IN(PH0)_5") (pintype "bidirectional"))
      (node (ref "X1") (pin "1") (pinfunction "OSC1_1") (pintype "input"))
    )
    (net (code "26") (name "Net-(U1A-PH1-OSC_OUT(PH1))") (class "Default")
      (node (ref "C20") (pin "2") (pinfunction "2_2") (pintype "unspecified"))
      (node (ref "U1") (pin "6") (pinfunction "PH1-OSC_OUT(PH1)_6") (pintype "bidirectional"))
      (node (ref "X1") (pin "3") (pinfunction "OSC2_3") (pintype "input"))
    )
    (net (code "27") (name "Net-(U1A-VCAP_1)") (class "Default")
      (node (ref "C17") (pin "1") (pinfunction "1_1") (pintype "input"))
      (node (ref "U1") (pin "31") (pinfunction "VCAP_1_31") (pintype "unspecified"))
    )
    (net (code "28") (name "Net-(U1A-VCAP_2)") (class "Default")
      (node (ref "C18") (pin "1") (pinfunction "1_1") (pintype "input"))
      (node (ref "U1") (pin "47") (pinfunction "VCAP_2_47") (pintype "unspecified"))
    )
    (net (code "29") (name "Net-(U1B-VDDA)") (class "Default")
      (node (ref "L2") (pin "1") (pinfunction "1_1") (pintype "unspecified"))
      (node (ref "U1") (pin "13") (pinfunction "VDDA_13") (pintype "unspecified"))
    )
    (net (code "30") (name "Net-(U2-BP)") (class "Default")
      (node (ref "C3") (pin "2") (pinfunction "2_2") (pintype "input"))
      (node (ref "U2") (pin "4") (pinfunction "BP_4") (pintype "unspecified"))
    )
    (net (code "31") (name "Net-(U4-BP)") (class "Default")
      (node (ref "C9") (pin "2") (pinfunction "2_2") (pintype "input"))
      (node (ref "U4") (pin "4") (pinfunction "BP_4") (pintype "unspecified"))
    )
    (net (code "32") (name "Net-(U5-SD)") (class "Default")
      (node (ref "R5") (pin "1") (pinfunction "1_1") (pintype "input"))
      (node (ref "U5") (pin "6") (pinfunction "SD_6") (pintype "unspecified"))
    )
    (net (code "33") (name "Net-(U6-SD)") (class "Default")
      (node (ref "R7") (pin "1") (pinfunction "1_1") (pintype "input"))
      (node (ref "U6") (pin "6") (pinfunction "SD_6") (pintype "unspecified"))
    )
    (net (code "34") (name "Net-(U7-SD)") (class "Default")
      (node (ref "R6") (pin "1") (pinfunction "1_1") (pintype "input"))
      (node (ref "U7") (pin "6") (pinfunction "SD_6") (pintype "unspecified"))
    )
    (net (code "35") (name "Net-(U8-SD)") (class "Default")
      (node (ref "R8") (pin "2") (pinfunction "2_2") (pintype "input"))
      (node (ref "U8") (pin "6") (pinfunction "SD_6") (pintype "unspecified"))
    )
    (net (code "36") (name "Net-(USBC1-CC1)") (class "Default")
      (node (ref "R1") (pin "2") (pinfunction "2_2") (pintype "input"))
      (node (ref "USBC1") (pin "A5") (pinfunction "CC1_A5") (pintype "unspecified"))
    )
    (net (code "37") (name "Net-(USBC1-CC2)") (class "Default")
      (node (ref "R2") (pin "2") (pinfunction "2_2") (pintype "input"))
      (node (ref "USBC1") (pin "B5") (pinfunction "CC2_B5") (pintype "unspecified"))
    )
    (net (code "38") (name "unconnected-(SW1-Pad2)") (class "Default")
      (node (ref "SW1") (pin "2") (pinfunction "2_2") (pintype "unspecified"))
    )
    (net (code "39") (name "unconnected-(SW1-Pad3)") (class "Default")
      (node (ref "SW1") (pin "3") (pinfunction "3_3") (pintype "unspecified"))
    )
    (net (code "40") (name "unconnected-(U1A-PA0-WKUP(PA0)-Pad14)") (class "Default")
      (node (ref "U1") (pin "14") (pinfunction "PA0-WKUP(PA0)_14") (pintype "bidirectional"))
    )
    (net (code "41") (name "unconnected-(U1A-PA1-Pad15)") (class "Default")
      (node (ref "U1") (pin "15") (pinfunction "PA1_15") (pintype "bidirectional"))
    )
    (net (code "42") (name "unconnected-(U1A-PA4-Pad20)") (class "Default")
      (node (ref "U1") (pin "20") (pinfunction "PA4_20") (pintype "bidirectional"))
    )
    (net (code "43") (name "unconnected-(U1A-PA5-Pad21)") (class "Default")
      (node (ref "U1") (pin "21") (pinfunction "PA5_21") (pintype "bidirectional"))
    )
    (net (code "44") (name "unconnected-(U1A-PA6-Pad22)") (class "Default")
      (node (ref "U1") (pin "22") (pinfunction "PA6_22") (pintype "bidirectional"))
    )
    (net (code "45") (name "unconnected-(U1A-PA7-Pad23)") (class "Default")
      (node (ref "U1") (pin "23") (pinfunction "PA7_23") (pintype "bidirectional"))
    )
    (net (code "46") (name "unconnected-(U1A-PA8-Pad41)") (class "Default")
      (node (ref "U1") (pin "41") (pinfunction "PA8_41") (pintype "bidirectional"))
    )
    (net (code "47") (name "unconnected-(U1A-PA15(JTDI)-Pad50)") (class "Default")
      (node (ref "U1") (pin "50") (pinfunction "PA15(JTDI)_50") (pintype "bidirectional"))
    )
    (net (code "48") (name "unconnected-(U1A-PB0-Pad26)") (class "Default")
      (node (ref "U1") (pin "26") (pinfunction "PB0_26") (pintype "bidirectional"))
    )
    (net (code "49") (name "unconnected-(U1A-PB1-Pad27)") (class "Default")
      (node (ref "U1") (pin "27") (pinfunction "PB1_27") (pintype "bidirectional"))
    )
    (net (code "50") (name "unconnected-(U1A-PB2-BOOT1(PB2)-Pad28)") (class "Default")
      (node (ref "U1") (pin "28") (pinfunction "PB2-BOOT1(PB2)_28") (pintype "bidirectional"))
    )
    (net (code "51") (name "unconnected-(U1A-PB3(JTDOTRACESWO)-Pad55)") (class "Default")
      (node (ref "U1") (pin "55") (pinfunction "PB3(JTDOTRACESWO)_55") (pintype "bidirectional"))
    )
    (net (code "52") (name "unconnected-(U1A-PB4(NJTRST)-Pad56)") (class "Default")
      (node (ref "U1") (pin "56") (pinfunction "PB4(NJTRST)_56") (pintype "bidirectional"))
    )
    (net (code "53") (name "unconnected-(U1A-PB5-Pad57)") (class "Default")
      (node (ref "U1") (pin "57") (pinfunction "PB5_57") (pintype "bidirectional"))
    )
    (net (code "54") (name "unconnected-(U1A-PB6-Pad58)") (class "Default")
      (node (ref "U1") (pin "58") (pinfunction "PB6_58") (pintype "bidirectional"))
    )
    (net (code "55") (name "unconnected-(U1A-PB7-Pad59)") (class "Default")
      (node (ref "U1") (pin "59") (pinfunction "PB7_59") (pintype "bidirectional"))
    )
    (net (code "56") (name "unconnected-(U1A-PB8-Pad61)") (class "Default")
      (node (ref "U1") (pin "61") (pinfunction "PB8_61") (pintype "bidirectional"))
    )
    (net (code "57") (name "unconnected-(U1A-PB9-Pad62)") (class "Default")
      (node (ref "U1") (pin "62") (pinfunction "PB9_62") (pintype "bidirectional"))
    )
    (net (code "58") (name "unconnected-(U1A-PB11-Pad30)") (class "Default")
      (node (ref "U1") (pin "30") (pinfunction "PB11_30") (pintype "bidirectional"))
    )
    (net (code "59") (name "unconnected-(U1A-PB13-Pad34)") (class "Default")
      (node (ref "U1") (pin "34") (pinfunction "PB13_34") (pintype "bidirectional"))
    )
    (net (code "60") (name "unconnected-(U1A-PB14-Pad35)") (class "Default")
      (node (ref "U1") (pin "35") (pinfunction "PB14_35") (pintype "bidirectional"))
    )
    (net (code "61") (name "unconnected-(U1A-PB15-Pad36)") (class "Default")
      (node (ref "U1") (pin "36") (pinfunction "PB15_36") (pintype "bidirectional"))
    )
    (net (code "62") (name "unconnected-(U1A-PC2-Pad10)") (class "Default")
      (node (ref "U1") (pin "10") (pinfunction "PC2_10") (pintype "bidirectional"))
    )
    (net (code "63") (name "unconnected-(U1A-PC4-Pad24)") (class "Default")
      (node (ref "U1") (pin "24") (pinfunction "PC4_24") (pintype "bidirectional"))
    )
    (net (code "64") (name "unconnected-(U1A-PC5-Pad25)") (class "Default")
      (node (ref "U1") (pin "25") (pinfunction "PC5_25") (pintype "bidirectional"))
    )
    (net (code "65") (name "unconnected-(U1A-PC6-Pad37)") (class "Default")
      (node (ref "U1") (pin "37") (pinfunction "PC6_37") (pintype "bidirectional"))
    )
    (net (code "66") (name "unconnected-(U1A-PC7-Pad38)") (class "Default")
      (node (ref "U1") (pin "38") (pinfunction "PC7_38") (pintype "bidirectional"))
    )
    (net (code "67") (name "unconnected-(U1A-PC8-Pad39)") (class "Default")
      (node (ref "U1") (pin "39") (pinfunction "PC8_39") (pintype "bidirectional"))
    )
    (net (code "68") (name "unconnected-(U1A-PC9-Pad40)") (class "Default")
      (node (ref "U1") (pin "40") (pinfunction "PC9_40") (pintype "bidirectional"))
    )
    (net (code "69") (name "unconnected-(U1A-PC10-Pad51)") (class "Default")
      (node (ref "U1") (pin "51") (pinfunction "PC10_51") (pintype "bidirectional"))
    )
    (net (code "70") (name "unconnected-(U1A-PC11-Pad52)") (class "Default")
      (node (ref "U1") (pin "52") (pinfunction "PC11_52") (pintype "bidirectional"))
    )
    (net (code "71") (name "unconnected-(U1A-PC13-Pad2)") (class "Default")
      (node (ref "U1") (pin "2") (pinfunction "PC13_2") (pintype "bidirectional"))
    )
    (net (code "72") (name "unconnected-(U1A-PC14-OSC32_IN(PC14)-Pad3)") (class "Default")
      (node (ref "U1") (pin "3") (pinfunction "PC14-OSC32_IN(PC14)_3") (pintype "bidirectional"))
    )
    (net (code "73") (name "unconnected-(U1A-PC15-OSC32_OUT(PC15)-Pad4)") (class "Default")
      (node (ref "U1") (pin "4") (pinfunction "PC15-OSC32_OUT(PC15)_4") (pintype "bidirectional"))
    )
    (net (code "74") (name "unconnected-(U1A-PD2-Pad54)") (class "Default")
      (node (ref "U1") (pin "54") (pinfunction "PD2_54") (pintype "bidirectional"))
    )
    (net (code "75") (name "unconnected-(U3-NC-Pad4)") (class "Default")
      (node (ref "U3") (pin "4") (pinfunction "NC_4") (pintype "unspecified"))
    )
    (net (code "76") (name "unconnected-(U5-GND-Pad3)") (class "Default")
      (node (ref "U5") (pin "3") (pinfunction "GND_3") (pintype "unspecified"))
    )
    (net (code "77") (name "unconnected-(U6-GND-Pad3)") (class "Default")
      (node (ref "U6") (pin "3") (pinfunction "GND_3") (pintype "unspecified"))
    )
    (net (code "78") (name "unconnected-(U9-DNC-Pad8)") (class "Default")
      (node (ref "U9") (pin "8") (pinfunction "DNC_8") (pintype "unspecified"))
    )
    (net (code "79") (name "unconnected-(USBC1-EH-Pad1)") (class "Default")
      (node (ref "USBC1") (pin "1") (pinfunction "EH_1") (pintype "unspecified"))
    )
    (net (code "80") (name "unconnected-(USBC1-EH-Pad2)") (class "Default")
      (node (ref "USBC1") (pin "2") (pinfunction "EH_2") (pintype "unspecified"))
    )
    (net (code "81") (name "unconnected-(USBC1-EH-Pad3)") (class "Default")
      (node (ref "USBC1") (pin "3") (pinfunction "EH_3") (pintype "unspecified"))
    )
    (net (code "82") (name "unconnected-(USBC1-EH-Pad4)") (class "Default")
      (node (ref "USBC1") (pin "4") (pinfunction "EH_4") (pintype "unspecified"))
    )
    (net (code "83") (name "unconnected-(USBC1-SBU1-PadA8)") (class "Default")
      (node (ref "USBC1") (pin "A8") (pinfunction "SBU1_A8") (pintype "unspecified"))
    )
    (net (code "84") (name "unconnected-(USBC1-SBU2-PadB8)") (class "Default")
      (node (ref "USBC1") (pin "B8") (pinfunction "SBU2_B8") (pintype "unspecified"))
    )
  )
)
